# design.net
KiCad netlist of a schematic drawn in Altium Designer
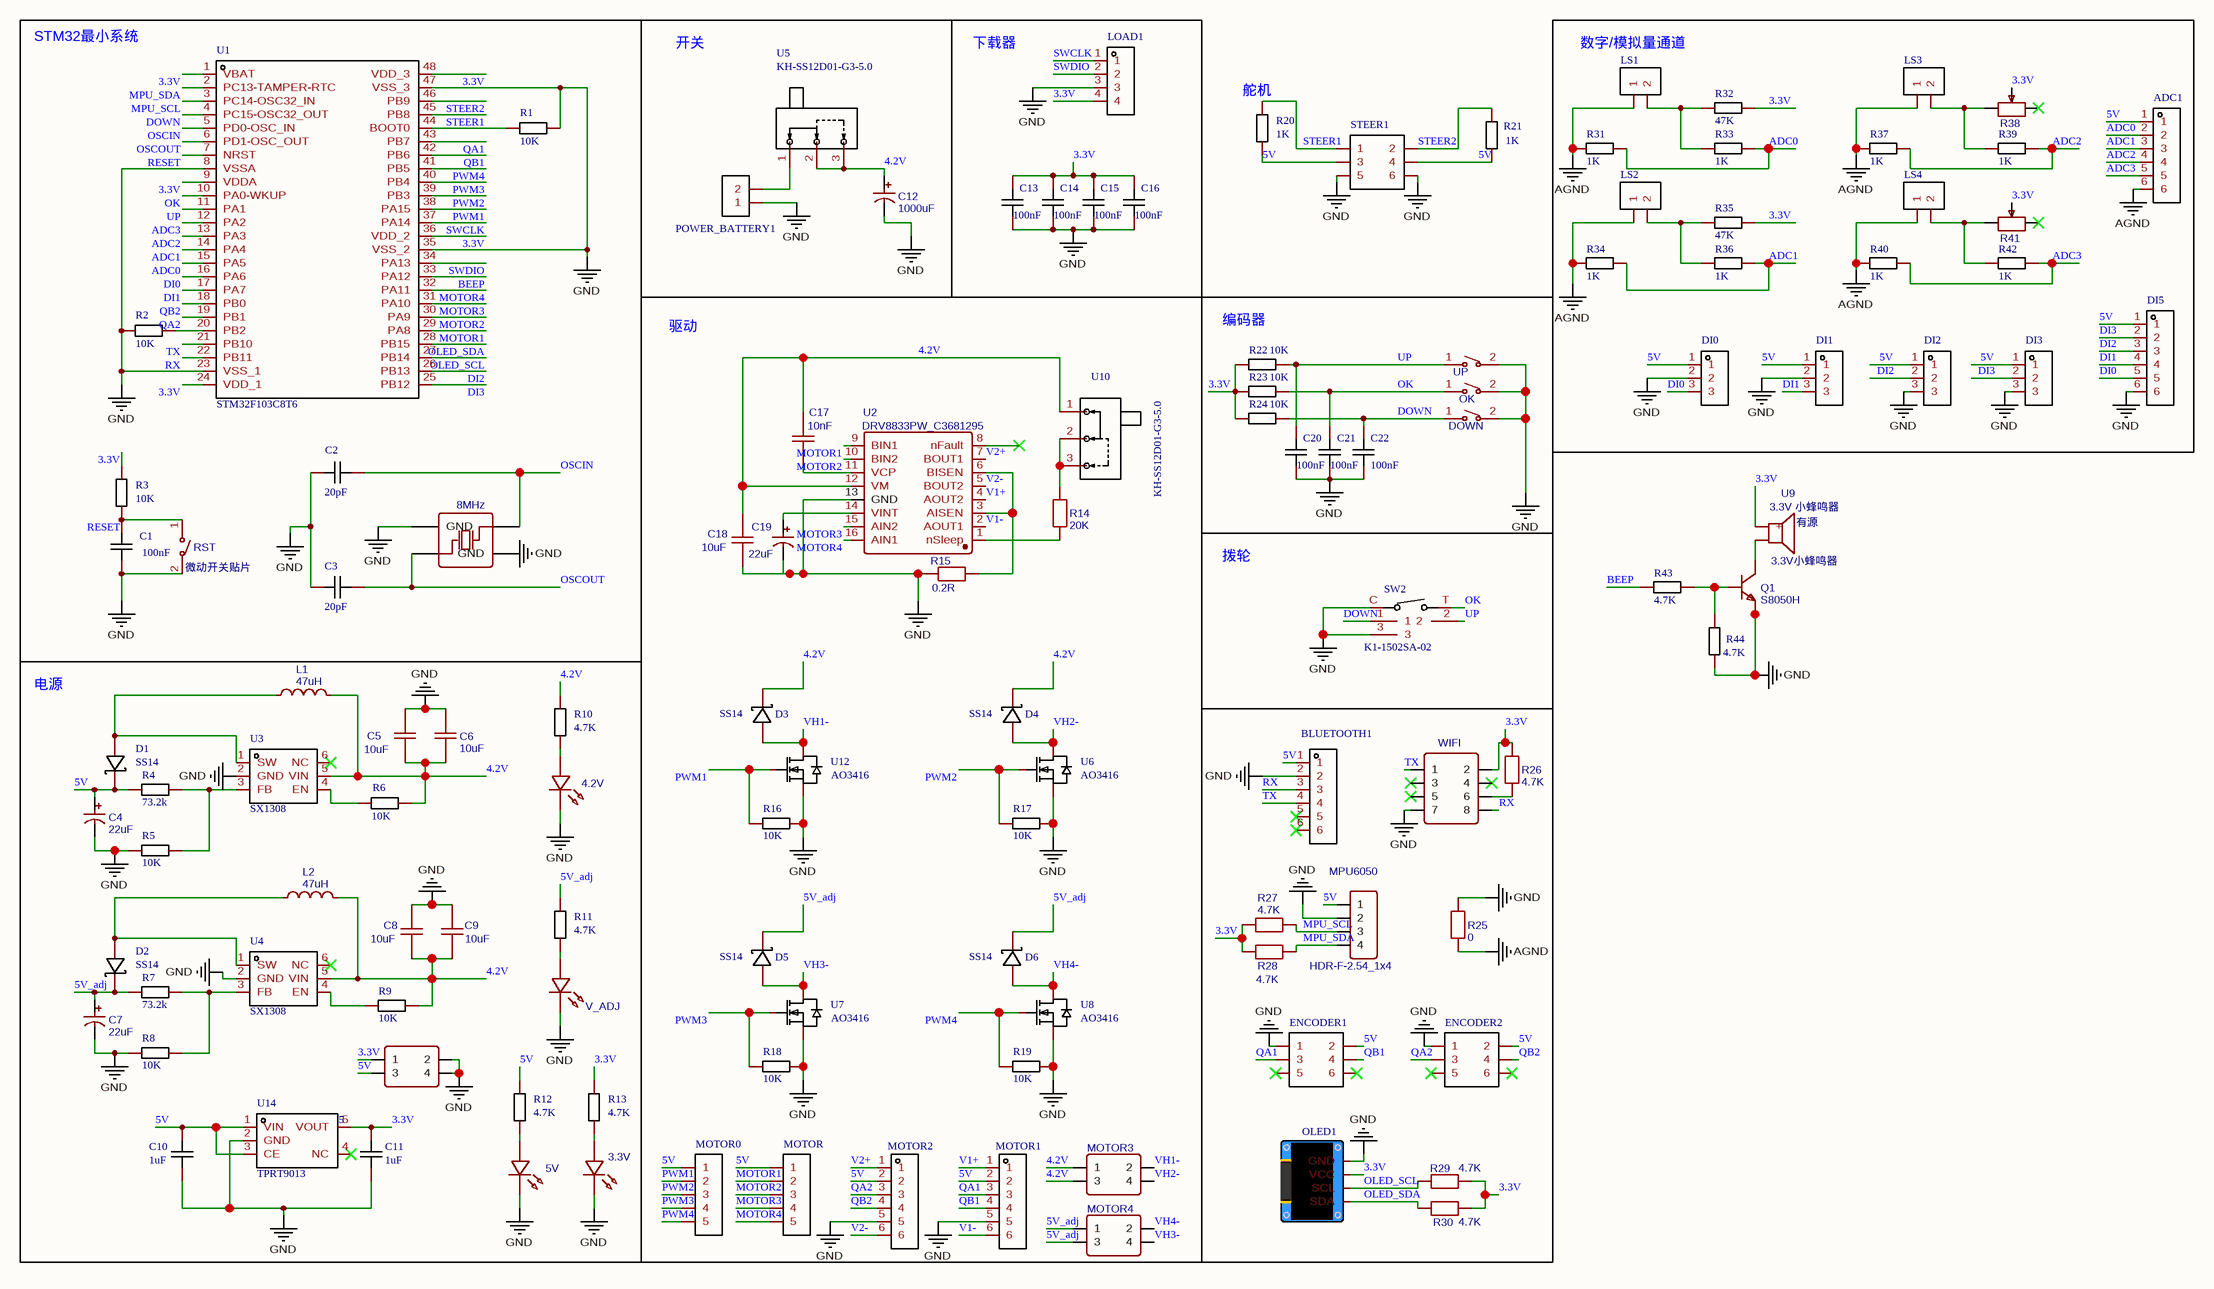
[diagram p0: 船主控原理图.schdoc]

(export (version "E")
  (design (tool "Eeschema 10.0.6"))
  (components
    (comp (ref "3.3V")
      (value "LED-0603_R")
      (fields
        (field (name "BOM_MANUFACTURER PART") "19-217/R6C-AL1M2VY/3T")
        (field (name "BOM_SUPPLIER PART") "C72044")
        (field (name "CONTRIBUTOR") "LCEDA_01")
      )
      (libsource (lib "altium-import") (part "root_3_LED-0603_R_"))
    )
    (comp (ref "4.2V")
      (value "LED-0603_R")
      (fields
        (field (name "BOM_MANUFACTURER PART") "19-217/R6C-AL1M2VY/3T")
        (field (name "BOM_SUPPLIER PART") "C72044")
        (field (name "CONTRIBUTOR") "LCEDA_01")
      )
      (libsource (lib "altium-import") (part "root_3_LED-0603_R_"))
    )
    (comp (ref "5V")
      (value "LED-0603_R")
      (fields
        (field (name "BOM_MANUFACTURER PART") "19-217/R6C-AL1M2VY/3T")
        (field (name "BOM_SUPPLIER PART") "C72044")
        (field (name "CONTRIBUTOR") "LCEDA_01")
      )
      (libsource (lib "altium-import") (part "root_3_LED-0603_R_"))
    )
    (comp (ref "ADC1")
      (value "HDR-F_2.54_1x6P")
      (libsource (lib "altium-import") (part "root_0_HDR-F_2.54_1x6P_"))
    )
    (comp (ref "BLUETOOTH1")
      (value "HDR-F_2.54_1x6P")
      (libsource (lib "altium-import") (part "root_0_HDR-F_2.54_1x6P_"))
    )
    (comp (ref "C1") (value "100nF") (libsource (lib "altium-import") (part "root_1_100nF_")))
    (comp (ref "C2") (value "100nF") (libsource (lib "altium-import") (part "root_0_100nF_")))
    (comp (ref "C3") (value "100nF") (libsource (lib "altium-import") (part "root_0_100nF_")))
    (comp (ref "C4")
      (value "22uF")
      (fields
        (field (name "BOM_MANUFACTURER PART") "CA45-A-6.3V-22uF-M")
        (field (name "BOM_SUPPLIER PART") "C140378")
        (field (name "CONTRIBUTOR") "LCSC")
      )
      (libsource (lib "altium-import") (part "root_1_22uF_"))
    )
    (comp (ref "C5")
      (value "10uF")
      (fields (field (name "CONTRIBUTOR") "LCEDA_Lib"))
      (libsource (lib "altium-import") (part "root_1_10uF_"))
    )
    (comp (ref "C6")
      (value "10uF")
      (fields (field (name "CONTRIBUTOR") "LCEDA_Lib"))
      (libsource (lib "altium-import") (part "root_1_10uF_"))
    )
    (comp (ref "C7")
      (value "22uF")
      (fields
        (field (name "BOM_MANUFACTURER PART") "CA45-A-6.3V-22uF-M")
        (field (name "BOM_SUPPLIER PART") "C140378")
        (field (name "CONTRIBUTOR") "LCSC")
      )
      (libsource (lib "altium-import") (part "root_1_22uF_"))
    )
    (comp (ref "C8")
      (value "10uF")
      (fields (field (name "CONTRIBUTOR") "LCEDA_Lib"))
      (libsource (lib "altium-import") (part "root_1_10uF_"))
    )
    (comp (ref "C9")
      (value "10uF")
      (fields (field (name "CONTRIBUTOR") "LCEDA_Lib"))
      (libsource (lib "altium-import") (part "root_1_10uF_"))
    )
    (comp (ref "C10") (value "1uF") (libsource (lib "altium-import") (part "root_1_1uF_")))
    (comp (ref "C11") (value "1uF") (libsource (lib "altium-import") (part "root_1_1uF_")))
    (comp (ref "C12")
      (value "1000uF")
      (fields
        (field (name "BOM_MANUFACTURER PART") "GR108M016F16RR0VL4FP0")
        (field (name "BOM_SUPPLIER PART") "C43834")
      )
      (libsource (lib "altium-import") (part "root_3_1000uF_"))
    )
    (comp (ref "C13") (value "100nF") (libsource (lib "altium-import") (part "root_1_100nF_")))
    (comp (ref "C14") (value "100nF") (libsource (lib "altium-import") (part "root_1_100nF_")))
    (comp (ref "C15") (value "100nF") (libsource (lib "altium-import") (part "root_1_100nF_")))
    (comp (ref "C16") (value "100nF") (libsource (lib "altium-import") (part "root_1_100nF_")))
    (comp (ref "C17")
      (value "10nF")
      (fields (field (name "CONTRIBUTOR") "LCEDA_Lib"))
      (libsource (lib "altium-import") (part "root_1_10nF_"))
    )
    (comp (ref "C18")
      (value "10uF")
      (fields (field (name "CONTRIBUTOR") "LCEDA_Lib"))
      (libsource (lib "altium-import") (part "root_1_10uF_"))
    )
    (comp (ref "C19")
      (value "22uF")
      (fields
        (field (name "BOM_MANUFACTURER PART") "CA45-A-6.3V-22uF-M")
        (field (name "BOM_SUPPLIER PART") "C140378")
        (field (name "CONTRIBUTOR") "LCSC")
      )
      (libsource (lib "altium-import") (part "root_1_22uF_"))
    )
    (comp (ref "C20") (value "100nF") (libsource (lib "altium-import") (part "root_1_100nF_")))
    (comp (ref "C21") (value "100nF") (libsource (lib "altium-import") (part "root_3_100nF_")))
    (comp (ref "C22") (value "100nF") (libsource (lib "altium-import") (part "root_1_100nF_")))
    (comp (ref "D1")
      (value "SS14")
      (fields (field (name "MANUFACTURER") "onsemi(安森美)"))
      (libsource (lib "altium-import") (part "root_1_SS14_"))
    )
    (comp (ref "D2")
      (value "SS14")
      (fields (field (name "MANUFACTURER") "onsemi(安森美)"))
      (libsource (lib "altium-import") (part "root_1_SS14_"))
    )
    (comp (ref "D3")
      (value "SS14")
      (fields (field (name "MANUFACTURER") "onsemi(安森美)"))
      (libsource (lib "altium-import") (part "root_3_SS14_"))
    )
    (comp (ref "D4")
      (value "SS14")
      (fields (field (name "MANUFACTURER") "onsemi(安森美)"))
      (libsource (lib "altium-import") (part "root_3_SS14_"))
    )
    (comp (ref "D5")
      (value "SS14")
      (fields (field (name "MANUFACTURER") "onsemi(安森美)"))
      (libsource (lib "altium-import") (part "root_3_SS14_"))
    )
    (comp (ref "D6")
      (value "SS14")
      (fields (field (name "MANUFACTURER") "onsemi(安森美)"))
      (libsource (lib "altium-import") (part "root_3_SS14_"))
    )
    (comp (ref "DI0")
      (value "HDR-F_2.54_1x3P")
      (libsource (lib "altium-import") (part "root_0_HDR-F_2.54_1x3P_"))
    )
    (comp (ref "DI1")
      (value "HDR-F_2.54_1x3P")
      (libsource (lib "altium-import") (part "root_0_HDR-F_2.54_1x3P_"))
    )
    (comp (ref "DI2")
      (value "HDR-F_2.54_1x3P")
      (libsource (lib "altium-import") (part "root_0_HDR-F_2.54_1x3P_"))
    )
    (comp (ref "DI3")
      (value "HDR-F_2.54_1x3P")
      (libsource (lib "altium-import") (part "root_0_HDR-F_2.54_1x3P_"))
    )
    (comp (ref "DI5")
      (value "HDR-F_2.54_1x6P")
      (libsource (lib "altium-import") (part "root_0_HDR-F_2.54_1x6P_"))
    )
    (comp (ref "DOWN")
      (value "微动开关贴片")
      (fields (field (name "BOM_SUPPLIER PART") "C9900003994") (field (name "CONTRIBUTOR") "LCSC"))
      (libsource (lib "altium-import") (part "root_0_微动开关贴片_"))
    )
    (comp (ref "ENCODER1")
      (value "HDR-F_2.54_2x3")
      (libsource (lib "altium-import") (part "root_0_HDR-F_2.54_2x3_"))
    )
    (comp (ref "ENCODER2")
      (value "HDR-F_2.54_2x3")
      (libsource (lib "altium-import") (part "root_0_HDR-F_2.54_2x3_"))
    )
    (comp (ref "H1")
      (value "HDR-F-2.54_2x2")
      (fields (field (name "BOM_SUPPLIER PART") "C239342") (field (name "CONTRIBUTOR") "LCEDA_Lib"))
      (libsource (lib "altium-import") (part "root_0_HDR-F-2.54_2x2_"))
    )
    (comp (ref "L1")
      (value "47uH")
      (fields
        (field (name "BOM_SUPPLIER PART") "C9900014391")
        (field (name "BOM_MANUFACTURER PART") "CDRH74R-7*7*4MM")
        (field (name "CONTRIBUTOR") "lcsc")
      )
      (libsource (lib "altium-import") (part "root_0_47uH_"))
    )
    (comp (ref "L2")
      (value "47uH")
      (fields
        (field (name "BOM_SUPPLIER PART") "C9900014391")
        (field (name "BOM_MANUFACTURER PART") "CDRH74R-7*7*4MM")
        (field (name "CONTRIBUTOR") "lcsc")
      )
      (libsource (lib "altium-import") (part "root_0_47uH_"))
    )
    (comp (ref "LOAD1")
      (value "HDR-F_2.54_1x4P")
      (libsource (lib "altium-import") (part "root_0_HDR-F_2.54_1x4P_"))
    )
    (comp (ref "LS1")
      (value "HDR-F_2.54_1x2P")
      (libsource (lib "altium-import") (part "root_1_HDR-F_2.54_1x2P_"))
    )
    (comp (ref "LS2")
      (value "HDR-F_2.54_1x2P")
      (libsource (lib "altium-import") (part "root_1_HDR-F_2.54_1x2P_"))
    )
    (comp (ref "LS3")
      (value "HDR-F_2.54_1x2P")
      (libsource (lib "altium-import") (part "root_1_HDR-F_2.54_1x2P_"))
    )
    (comp (ref "LS4")
      (value "HDR-F_2.54_1x2P")
      (libsource (lib "altium-import") (part "root_1_HDR-F_2.54_1x2P_"))
    )
    (comp (ref "MOTOR")
      (value "HDR-F_2.54_1x5P")
      (libsource (lib "altium-import") (part "root_0_HDR-F_2.54_1x5P_"))
    )
    (comp (ref "MOTOR0")
      (value "HDR-F_2.54_1x5P")
      (libsource (lib "altium-import") (part "root_0_HDR-F_2.54_1x5P_"))
    )
    (comp (ref "MOTOR1") (value "HDR-F_2.54_1x6P") (libsource (lib "") (part "root_0_HDR-F_2.54_1x6P__1")))
    (comp (ref "MOTOR2") (value "HDR-F_2.54_1x6P") (libsource (lib "") (part "root_0_HDR-F_2.54_1x6P__1")))
    (comp (ref "MOTOR3")
      (value "HDR-F-2.54_2x2")
      (fields (field (name "BOM_SUPPLIER PART") "C239342") (field (name "CONTRIBUTOR") "LCEDA_Lib"))
      (libsource (lib "altium-import") (part "root_0_HDR-F-2.54_2x2_"))
    )
    (comp (ref "MOTOR4")
      (value "HDR-F-2.54_2x2")
      (fields (field (name "BOM_SUPPLIER PART") "C239342") (field (name "CONTRIBUTOR") "LCEDA_Lib"))
      (libsource (lib "altium-import") (part "root_0_HDR-F-2.54_2x2_"))
    )
    (comp (ref "MPU6050")
      (value "HDR-F-2.54_1x4")
      (fields (field (name "BOM_SUPPLIER PART") "C225501") (field (name "CONTRIBUTOR") "LCEDA_Lib"))
      (libsource (lib "altium-import") (part "root_0_HDR-F-2.54_1x4_"))
    )
    (comp (ref "NO1")
      (value "8MHz")
      (fields
        (field (name "BOM_MANUFACTURER PART") "8M-3225G封装")
        (field (name "BOM_SUPPLIER PART") "无源晶振8M-3225")
        (field (name "CONTRIBUTOR") "BaoXiWang")
      )
      (libsource (lib "altium-import") (part "root_0_8MHz_"))
    )
    (comp (ref "OK")
      (value "微动开关贴片")
      (fields (field (name "BOM_SUPPLIER PART") "C9900003994") (field (name "CONTRIBUTOR") "LCSC"))
      (libsource (lib "altium-import") (part "root_0_微动开关贴片_"))
    )
    (comp (ref "OLED1")
      (value "0.96OLED模块_4P")
      (libsource (lib "altium-import") (part "root_3_0.96OLED模块_4P_"))
    )
    (comp (ref "POWER_BATTERY1")
      (value "HDR-F_2.54_1x2P")
      (libsource (lib "altium-import") (part "root_2_HDR-F_2.54_1x2P_"))
    )
    (comp (ref "Q1")
      (value "S8050H")
      (fields (field (name "BOM_SUPPLIER PART") "C388539") (field (name "CONTRIBUTOR") "LCSC"))
      (libsource (lib "altium-import") (part "root_0_S8050H_"))
    )
    (comp (ref "R1") (value "10K") (libsource (lib "altium-import") (part "root_0_10K_")))
    (comp (ref "R2") (value "10K") (libsource (lib "altium-import") (part "root_0_10K_")))
    (comp (ref "R3") (value "10K") (libsource (lib "altium-import") (part "root_1_10K_")))
    (comp (ref "R4") (value "3K") (libsource (lib "altium-import") (part "root_2_3K_")))
    (comp (ref "R5") (value "2K") (libsource (lib "altium-import") (part "root_2_2K_")))
    (comp (ref "R6") (value "10K") (libsource (lib "altium-import") (part "root_2_10K_")))
    (comp (ref "R7") (value "1K") (libsource (lib "altium-import") (part "root_2_1K_")))
    (comp (ref "R8") (value "3K") (libsource (lib "altium-import") (part "root_2_3K_")))
    (comp (ref "R9") (value "10K") (libsource (lib "altium-import") (part "root_2_10K_")))
    (comp (ref "R10") (value "4.7K") (libsource (lib "altium-import") (part "root_1_4.7K_")))
    (comp (ref "R11") (value "4.7K") (libsource (lib "altium-import") (part "root_1_4.7K_")))
    (comp (ref "R12") (value "4.7K") (libsource (lib "altium-import") (part "root_1_4.7K_")))
    (comp (ref "R13") (value "4.7K") (libsource (lib "altium-import") (part "root_1_4.7K_")))
    (comp (ref "R14")
      (value "20K")
      (fields (field (name "CONTRIBUTOR") "LCEDA_Lib"))
      (libsource (lib "altium-import") (part "root_1_20K_"))
    )
    (comp (ref "R15")
      (value "0.2R")
      (fields (field (name "CONTRIBUTOR") "LCEDA_Lib"))
      (libsource (lib "altium-import") (part "root_0_0.2R_"))
    )
    (comp (ref "R16") (value "10K") (libsource (lib "altium-import") (part "root_2_10K_")))
    (comp (ref "R17") (value "10K") (libsource (lib "altium-import") (part "root_2_10K_")))
    (comp (ref "R18") (value "10K") (libsource (lib "altium-import") (part "root_2_10K_")))
    (comp (ref "R19") (value "10K") (libsource (lib "altium-import") (part "root_2_10K_")))
    (comp (ref "R20") (value "1K") (libsource (lib "altium-import") (part "root_3_1K_")))
    (comp (ref "R21") (value "1K") (libsource (lib "altium-import") (part "root_3_1K_")))
    (comp (ref "R22") (value "10K") (libsource (lib "altium-import") (part "root_2_10K_")))
    (comp (ref "R23") (value "10K") (libsource (lib "altium-import") (part "root_2_10K_")))
    (comp (ref "R24") (value "10K") (libsource (lib "altium-import") (part "root_2_10K_")))
    (comp (ref "R25")
      (value "0")
      (fields (field (name "CONTRIBUTOR") "LCEDA_Lib"))
      (libsource (lib "altium-import") (part "root_1_0_"))
    )
    (comp (ref "R26")
      (value "4.7K")
      (fields (field (name "CONTRIBUTOR") "LCEDA_Lib"))
      (libsource (lib "") (part "root_1_4.7K__1"))
    )
    (comp (ref "R27")
      (value "4.7K")
      (fields (field (name "CONTRIBUTOR") "LCEDA_Lib"))
      (libsource (lib "altium-import") (part "root_0_4.7K_"))
    )
    (comp (ref "R28")
      (value "4.7K")
      (fields (field (name "CONTRIBUTOR") "LCEDA_Lib"))
      (libsource (lib "altium-import") (part "root_0_4.7K_"))
    )
    (comp (ref "R29")
      (value "4.7K")
      (fields (field (name "CONTRIBUTOR") "LCEDA_Lib"))
      (libsource (lib "altium-import") (part "root_2_4.7K_"))
    )
    (comp (ref "R30")
      (value "4.7K")
      (fields (field (name "CONTRIBUTOR") "LCEDA_Lib"))
      (libsource (lib "altium-import") (part "root_2_4.7K_"))
    )
    (comp (ref "R31") (value "1K") (libsource (lib "altium-import") (part "root_0_1K_")))
    (comp (ref "R32") (value "47K") (libsource (lib "altium-import") (part "root_2_47K_")))
    (comp (ref "R33") (value "1K") (libsource (lib "altium-import") (part "root_0_1K_")))
    (comp (ref "R34") (value "1K") (libsource (lib "altium-import") (part "root_0_1K_")))
    (comp (ref "R35") (value "47K") (libsource (lib "altium-import") (part "root_2_47K_")))
    (comp (ref "R36") (value "1K") (libsource (lib "altium-import") (part "root_0_1K_")))
    (comp (ref "R37") (value "1K") (libsource (lib "altium-import") (part "root_0_1K_")))
    (comp (ref "R38")
      (value "3296W-2K")
      (fields (field (name "BOM_SUPPLIER PART") "C9900022608") (field (name "CONTRIBUTOR") "lcsc"))
      (libsource (lib "altium-import") (part "root_3_3296W-2K_"))
    )
    (comp (ref "R39") (value "1K") (libsource (lib "altium-import") (part "root_0_1K_")))
    (comp (ref "R40") (value "1K") (libsource (lib "altium-import") (part "root_0_1K_")))
    (comp (ref "R41")
      (value "3296W-2K")
      (fields (field (name "BOM_SUPPLIER PART") "C9900022608") (field (name "CONTRIBUTOR") "lcsc"))
      (libsource (lib "altium-import") (part "root_3_3296W-2K_"))
    )
    (comp (ref "R42") (value "1K") (libsource (lib "altium-import") (part "root_0_1K_")))
    (comp (ref "R43") (value "1K") (libsource (lib "altium-import") (part "root_0_1K_")))
    (comp (ref "R44") (value "1K") (libsource (lib "altium-import") (part "root_1_1K_")))
    (comp (ref "RST")
      (value "微动开关贴片")
      (fields (field (name "BOM_SUPPLIER PART") "C9900003994") (field (name "CONTRIBUTOR") "LCSC"))
      (libsource (lib "altium-import") (part "root_3_微动开关贴片_"))
    )
    (comp (ref "STEER1")
      (value "HDR-F_2.54_2x3")
      (libsource (lib "altium-import") (part "root_0_HDR-F_2.54_2x3_"))
    )
    (comp (ref "SW2")
      (value "K1-1502SA-02")
      (fields (field (name "MANUFACTURER") "韩国韩荣"))
      (libsource (lib "altium-import") (part "root_0_K1-1502SA-02_"))
    )
    (comp (ref "U1")
      (value "STM32F103C8T6")
      (fields (field (name "MANUFACTURER") "ST(意法半导体)"))
      (libsource (lib "altium-import") (part "root_0_STM32F103C8T6_"))
    )
    (comp (ref "U2")
      (value "DRV8833PW_C3681295")
      (fields
        (field (name "BOM_SUPPLIER PART") "C3681295")
        (field (name "BOM_MANUFACTURER PART") "DRV8833PW")
        (field (name "CONTRIBUTOR") "lcsc")
      )
      (libsource (lib "altium-import") (part "root_2_DRV8833PW_C3681295_"))
    )
    (comp (ref "U3")
      (value "SX1308")
      (fields (field (name "MANUFACTURER") "SX(硕芯科技)"))
      (libsource (lib "altium-import") (part "root_0_SX1308_"))
    )
    (comp (ref "U4")
      (value "SX1308")
      (fields (field (name "MANUFACTURER") "SX(硕芯科技)"))
      (libsource (lib "altium-import") (part "root_0_SX1308_"))
    )
    (comp (ref "U5")
      (value "KH-SS12D01-G3-5.0")
      (fields (field (name "MANUFACTURER") "kinghelm(金航标)"))
      (libsource (lib "altium-import") (part "root_0_KH-SS12D01-G3-5.0_"))
    )
    (comp (ref "U6")
      (value "AO3416")
      (fields (field (name "MANUFACTURER") "BORN(伯恩半导体)"))
      (libsource (lib "altium-import") (part "root_0_AO3416_"))
    )
    (comp (ref "U7")
      (value "AO3416")
      (fields (field (name "MANUFACTURER") "BORN(伯恩半导体)"))
      (libsource (lib "altium-import") (part "root_0_AO3416_"))
    )
    (comp (ref "U8")
      (value "AO3416")
      (fields (field (name "MANUFACTURER") "BORN(伯恩半导体)"))
      (libsource (lib "altium-import") (part "root_0_AO3416_"))
    )
    (comp (ref "U9")
      (value "3.3V 小蜂鸣器")
      (fields (field (name "CONTRIBUTOR") "oyhoyh"))
      (libsource (lib "altium-import") (part "root_0_3.3V 小蜂鸣器_"))
    )
    (comp (ref "U10")
      (value "KH-SS12D01-G3-5.0")
      (fields (field (name "MANUFACTURER") "kinghelm(金航标)"))
      (libsource (lib "altium-import") (part "root_3_KH-SS12D01-G3-5.0_"))
    )
    (comp (ref "U12")
      (value "AO3416")
      (fields (field (name "MANUFACTURER") "BORN(伯恩半导体)"))
      (libsource (lib "altium-import") (part "root_0_AO3416_"))
    )
    (comp (ref "U14")
      (value "TPRT9013")
      (fields (field (name "MANUFACTURER") "TECH PUBLIC(台舟)"))
      (libsource (lib "altium-import") (part "root_0_TPRT9013_"))
    )
    (comp (ref "UP")
      (value "微动开关贴片")
      (fields (field (name "BOM_SUPPLIER PART") "C9900003994") (field (name "CONTRIBUTOR") "LCSC"))
      (libsource (lib "altium-import") (part "root_0_微动开关贴片_"))
    )
    (comp (ref "V_ADJ")
      (value "LED-0603_R")
      (fields
        (field (name "BOM_MANUFACTURER PART") "19-217/R6C-AL1M2VY/3T")
        (field (name "BOM_SUPPLIER PART") "C72044")
        (field (name "CONTRIBUTOR") "LCEDA_01")
      )
      (libsource (lib "altium-import") (part "root_3_LED-0603_R_"))
    )
    (comp (ref "WIFI")
      (value "HDR-M-2.54_2x4")
      (fields (field (name "BOM_SUPPLIER PART") "C58363") (field (name "CONTRIBUTOR") "LCEDA_Lib"))
      (libsource (lib "altium-import") (part "root_0_HDR-M-2.54_2x4_"))
    )
  )
  (nets
    (net (code "1") (name "/3.3V") (class "Default")
      (node (ref "C11") (pin "2") (pinfunction "2_2") (pintype "passive"))
      (node (ref "C13") (pin "2") (pinfunction "2_2") (pintype "passive"))
      (node (ref "C14") (pin "2") (pinfunction "2_2") (pintype "passive"))
      (node (ref "C15") (pin "2") (pinfunction "2_2") (pintype "passive"))
      (node (ref "C16") (pin "2") (pinfunction "2_2") (pintype "passive"))
      (node (ref "H1") (pin "1") (pinfunction "1_1") (pintype "passive"))
      (node (ref "LOAD1") (pin "4") (pinfunction "4_4") (pintype "passive"))
      (node (ref "OLED1") (pin "2") (pinfunction "VCC_2") (pintype "passive"))
      (node (ref "R13") (pin "2") (pinfunction "2_2") (pintype "passive"))
      (node (ref "R22") (pin "2") (pinfunction "2_2") (pintype "passive"))
      (node (ref "R23") (pin "2") (pinfunction "2_2") (pintype "passive"))
      (node (ref "R24") (pin "2") (pinfunction "2_2") (pintype "passive"))
      (node (ref "R26") (pin "2") (pinfunction "2_2") (pintype "passive"))
      (node (ref "R27") (pin "1") (pinfunction "1_1") (pintype "passive"))
      (node (ref "R28") (pin "1") (pinfunction "1_1") (pintype "passive"))
      (node (ref "R29") (pin "1") (pinfunction "1_1") (pintype "passive"))
      (node (ref "R3") (pin "2") (pinfunction "2_2") (pintype "passive"))
      (node (ref "R30") (pin "1") (pinfunction "1_1") (pintype "passive"))
      (node (ref "R32") (pin "1") (pinfunction "1_1") (pintype "passive"))
      (node (ref "R35") (pin "1") (pinfunction "1_1") (pintype "passive"))
      (node (ref "R38") (pin "2") (pinfunction "2_2") (pintype "passive"))
      (node (ref "R41") (pin "2") (pinfunction "2_2") (pintype "passive"))
      (node (ref "U1") (pin "1") (pinfunction "VBAT_1") (pintype "passive"))
      (node (ref "U1") (pin "24") (pinfunction "VDD_1_24") (pintype "passive"))
      (node (ref "U1") (pin "36") (pinfunction "VDD_2_36") (pintype "passive"))
      (node (ref "U1") (pin "48") (pinfunction "VDD_3_48") (pintype "passive"))
      (node (ref "U1") (pin "9") (pinfunction "VDDA_9") (pintype "passive"))
      (node (ref "U14") (pin "5") (pinfunction "VOUT_5") (pintype "passive"))
      (node (ref "U9") (pin "1") (pinfunction "+_1") (pintype "passive"))
      (node (ref "WIFI") (pin "2") (pinfunction "2_2") (pintype "passive"))
    )
    (net (code "2") (name "/4.2V") (class "Default")
      (node (ref "C12") (pin "1") (pinfunction "1_1") (pintype "passive"))
      (node (ref "C17") (pin "2") (pinfunction "2_2") (pintype "passive"))
      (node (ref "C18") (pin "2") (pinfunction "2_2") (pintype "passive"))
      (node (ref "C5") (pin "1") (pinfunction "1_1") (pintype "passive"))
      (node (ref "C6") (pin "1") (pinfunction "1_1") (pintype "passive"))
      (node (ref "C8") (pin "1") (pinfunction "1_1") (pintype "passive"))
      (node (ref "C9") (pin "1") (pinfunction "1_1") (pintype "passive"))
      (node (ref "D3") (pin "1") (pinfunction "K_1") (pintype "passive"))
      (node (ref "D4") (pin "1") (pinfunction "K_1") (pintype "passive"))
      (node (ref "L1") (pin "2") (pinfunction "2_2") (pintype "passive"))
      (node (ref "L2") (pin "2") (pinfunction "2_2") (pintype "passive"))
      (node (ref "MOTOR3") (pin "1") (pinfunction "1_1") (pintype "passive"))
      (node (ref "MOTOR3") (pin "3") (pinfunction "3_3") (pintype "passive"))
      (node (ref "R10") (pin "2") (pinfunction "2_2") (pintype "passive"))
      (node (ref "R6") (pin "1") (pinfunction "1_1") (pintype "passive"))
      (node (ref "R9") (pin "1") (pinfunction "1_1") (pintype "passive"))
      (node (ref "U10") (pin "1") (pinfunction "1_1") (pintype "passive"))
      (node (ref "U2") (pin "12") (pinfunction "VM_12") (pintype "passive"))
      (node (ref "U3") (pin "5") (pinfunction "VIN_5") (pintype "passive"))
      (node (ref "U4") (pin "5") (pinfunction "VIN_5") (pintype "passive"))
      (node (ref "U5") (pin "2") (pinfunction "2_2") (pintype "passive"))
      (node (ref "U5") (pin "3") (pinfunction "3_3") (pintype "passive"))
    )
    (net (code "3") (name "/5V") (class "Default")
      (node (ref "ADC1") (pin "1") (pinfunction "1_1") (pintype "passive"))
      (node (ref "BLUETOOTH1") (pin "1") (pinfunction "1_1") (pintype "passive"))
      (node (ref "C10") (pin "2") (pinfunction "2_2") (pintype "passive"))
      (node (ref "C4") (pin "1") (pinfunction "1_1") (pintype "passive"))
      (node (ref "D1") (pin "1") (pinfunction "K_1") (pintype "passive"))
      (node (ref "DI0") (pin "1") (pinfunction "1_1") (pintype "passive"))
      (node (ref "DI1") (pin "1") (pinfunction "1_1") (pintype "passive"))
      (node (ref "DI2") (pin "1") (pinfunction "1_1") (pintype "passive"))
      (node (ref "DI3") (pin "1") (pinfunction "1_1") (pintype "passive"))
      (node (ref "DI5") (pin "1") (pinfunction "1_1") (pintype "passive"))
      (node (ref "ENCODER1") (pin "2") (pinfunction "2_2") (pintype "passive"))
      (node (ref "ENCODER2") (pin "2") (pinfunction "2_2") (pintype "passive"))
      (node (ref "H1") (pin "3") (pinfunction "3_3") (pintype "passive"))
      (node (ref "MOTOR") (pin "1") (pinfunction "1_1") (pintype "passive"))
      (node (ref "MOTOR0") (pin "1") (pinfunction "1_1") (pintype "passive"))
      (node (ref "MOTOR1") (pin "2") (pinfunction "2_2") (pintype "passive"))
      (node (ref "MOTOR2") (pin "2") (pinfunction "2_2") (pintype "passive"))
      (node (ref "MPU6050") (pin "1") (pinfunction "1_1") (pintype "passive"))
      (node (ref "R12") (pin "2") (pinfunction "2_2") (pintype "passive"))
      (node (ref "R20") (pin "2") (pinfunction "2_2") (pintype "passive"))
      (node (ref "R21") (pin "2") (pinfunction "2_2") (pintype "passive"))
      (node (ref "R4") (pin "2") (pinfunction "2_2") (pintype "passive"))
      (node (ref "STEER1") (pin "3") (pinfunction "3_3") (pintype "passive"))
      (node (ref "STEER1") (pin "4") (pinfunction "4_4") (pintype "passive"))
      (node (ref "U14") (pin "1") (pinfunction "VIN_1") (pintype "passive"))
      (node (ref "U14") (pin "3") (pinfunction "CE_3") (pintype "passive"))
    )
    (net (code "4") (name "/5V_adj") (class "Default")
      (node (ref "C7") (pin "1") (pinfunction "1_1") (pintype "passive"))
      (node (ref "D2") (pin "1") (pinfunction "K_1") (pintype "passive"))
      (node (ref "D5") (pin "1") (pinfunction "K_1") (pintype "passive"))
      (node (ref "D6") (pin "1") (pinfunction "K_1") (pintype "passive"))
      (node (ref "MOTOR4") (pin "1") (pinfunction "1_1") (pintype "passive"))
      (node (ref "MOTOR4") (pin "3") (pinfunction "3_3") (pintype "passive"))
      (node (ref "R11") (pin "2") (pinfunction "2_2") (pintype "passive"))
      (node (ref "R7") (pin "2") (pinfunction "2_2") (pintype "passive"))
    )
    (net (code "5") (name "/ADC0") (class "Default")
      (node (ref "ADC1") (pin "2") (pinfunction "2_2") (pintype "passive"))
      (node (ref "R31") (pin "2") (pinfunction "2_2") (pintype "passive"))
      (node (ref "R33") (pin "2") (pinfunction "2_2") (pintype "passive"))
      (node (ref "U1") (pin "15") (pinfunction "PA5_15") (pintype "passive"))
    )
    (net (code "6") (name "/ADC1") (class "Default")
      (node (ref "ADC1") (pin "3") (pinfunction "3_3") (pintype "passive"))
      (node (ref "R34") (pin "2") (pinfunction "2_2") (pintype "passive"))
      (node (ref "R36") (pin "2") (pinfunction "2_2") (pintype "passive"))
      (node (ref "U1") (pin "14") (pinfunction "PA4_14") (pintype "passive"))
    )
    (net (code "7") (name "/ADC2") (class "Default")
      (node (ref "ADC1") (pin "4") (pinfunction "4_4") (pintype "passive"))
      (node (ref "R37") (pin "2") (pinfunction "2_2") (pintype "passive"))
      (node (ref "R39") (pin "2") (pinfunction "2_2") (pintype "passive"))
      (node (ref "U1") (pin "13") (pinfunction "PA3_13") (pintype "passive"))
    )
    (net (code "8") (name "/ADC3") (class "Default")
      (node (ref "ADC1") (pin "5") (pinfunction "5_5") (pintype "passive"))
      (node (ref "R40") (pin "2") (pinfunction "2_2") (pintype "passive"))
      (node (ref "R42") (pin "2") (pinfunction "2_2") (pintype "passive"))
      (node (ref "U1") (pin "12") (pinfunction "PA2_12") (pintype "passive"))
    )
    (net (code "9") (name "/BEEP") (class "Default")
      (node (ref "R43") (pin "1") (pinfunction "1_1") (pintype "passive"))
      (node (ref "U1") (pin "33") (pinfunction "PA12_33") (pintype "passive"))
    )
    (net (code "10") (name "/DI0") (class "Default")
      (node (ref "DI0") (pin "3") (pinfunction "3_3") (pintype "passive"))
      (node (ref "DI5") (pin "5") (pinfunction "5_5") (pintype "passive"))
      (node (ref "U1") (pin "16") (pinfunction "PA6_16") (pintype "passive"))
    )
    (net (code "11") (name "/DI1") (class "Default")
      (node (ref "DI1") (pin "3") (pinfunction "3_3") (pintype "passive"))
      (node (ref "DI5") (pin "4") (pinfunction "4_4") (pintype "passive"))
      (node (ref "U1") (pin "17") (pinfunction "PA7_17") (pintype "passive"))
    )
    (net (code "12") (name "/DI2") (class "Default")
      (node (ref "DI2") (pin "2") (pinfunction "2_2") (pintype "passive"))
      (node (ref "DI5") (pin "3") (pinfunction "3_3") (pintype "passive"))
      (node (ref "U1") (pin "26") (pinfunction "PB13_26") (pintype "passive"))
    )
    (net (code "13") (name "/DI3") (class "Default")
      (node (ref "DI3") (pin "2") (pinfunction "2_2") (pintype "passive"))
      (node (ref "DI5") (pin "2") (pinfunction "2_2") (pintype "passive"))
      (node (ref "U1") (pin "25") (pinfunction "PB12_25") (pintype "passive"))
    )
    (net (code "14") (name "/DOWN") (class "Default")
      (node (ref "C22") (pin "2") (pinfunction "2_2") (pintype "passive"))
      (node (ref "DOWN") (pin "1") (pinfunction "1_1") (pintype "passive"))
      (node (ref "R24") (pin "1") (pinfunction "1_1") (pintype "passive"))
      (node (ref "SW2") (pin "1") (pinfunction "1_1") (pintype "passive"))
      (node (ref "U1") (pin "4") (pinfunction "PC15-OSC32_OUT_4") (pintype "passive"))
    )
    (net (code "15") (name "/MOTOR1") (class "Default")
      (node (ref "MOTOR") (pin "2") (pinfunction "2_2") (pintype "passive"))
      (node (ref "U1") (pin "29") (pinfunction "PA8_29") (pintype "passive"))
      (node (ref "U2") (pin "9") (pinfunction "BIN1_9") (pintype "passive"))
    )
    (net (code "16") (name "/MOTOR2") (class "Default")
      (node (ref "MOTOR") (pin "3") (pinfunction "3_3") (pintype "passive"))
      (node (ref "U1") (pin "30") (pinfunction "PA9_30") (pintype "passive"))
      (node (ref "U2") (pin "10") (pinfunction "BIN2_10") (pintype "passive"))
    )
    (net (code "17") (name "/MOTOR3") (class "Default")
      (node (ref "MOTOR") (pin "4") (pinfunction "4_4") (pintype "passive"))
      (node (ref "U1") (pin "31") (pinfunction "PA10_31") (pintype "passive"))
      (node (ref "U2") (pin "15") (pinfunction "AIN2_15") (pintype "passive"))
    )
    (net (code "18") (name "/MOTOR4") (class "Default")
      (node (ref "MOTOR") (pin "5") (pinfunction "5_5") (pintype "passive"))
      (node (ref "U1") (pin "32") (pinfunction "PA11_32") (pintype "passive"))
      (node (ref "U2") (pin "16") (pinfunction "AIN1_16") (pintype "passive"))
    )
    (net (code "19") (name "/MPU_SCL") (class "Default")
      (node (ref "MPU6050") (pin "3") (pinfunction "3_3") (pintype "passive"))
      (node (ref "R27") (pin "2") (pinfunction "2_2") (pintype "passive"))
      (node (ref "U1") (pin "3") (pinfunction "PC14-OSC32_IN_3") (pintype "passive"))
    )
    (net (code "20") (name "/MPU_SDA") (class "Default")
      (node (ref "MPU6050") (pin "4") (pinfunction "4_4") (pintype "passive"))
      (node (ref "R28") (pin "2") (pinfunction "2_2") (pintype "passive"))
      (node (ref "U1") (pin "2") (pinfunction "PC13-TAMPER-RTC_2") (pintype "passive"))
    )
    (net (code "21") (name "/OK") (class "Default")
      (node (ref "C21") (pin "1") (pinfunction "1_1") (pintype "passive"))
      (node (ref "OK") (pin "1") (pinfunction "1_1") (pintype "passive"))
      (node (ref "R23") (pin "1") (pinfunction "1_1") (pintype "passive"))
      (node (ref "SW2") (pin "T") (pinfunction "T_T") (pintype "passive"))
      (node (ref "U1") (pin "10") (pinfunction "PA0-WKUP_10") (pintype "passive"))
    )
    (net (code "22") (name "/OLED_SCL") (class "Default")
      (node (ref "OLED1") (pin "3") (pinfunction "SCL_3") (pintype "passive"))
      (node (ref "R29") (pin "2") (pinfunction "2_2") (pintype "passive"))
      (node (ref "U1") (pin "27") (pinfunction "PB14_27") (pintype "passive"))
    )
    (net (code "23") (name "/OLED_SDA") (class "Default")
      (node (ref "OLED1") (pin "4") (pinfunction "SDA_4") (pintype "passive"))
      (node (ref "R30") (pin "2") (pinfunction "2_2") (pintype "passive"))
      (node (ref "U1") (pin "28") (pinfunction "PB15_28") (pintype "passive"))
    )
    (net (code "24") (name "/OSCIN") (class "Default")
      (node (ref "C2") (pin "2") (pinfunction "2_2") (pintype "passive"))
      (node (ref "NO1") (pin "3") (pinfunction "OSC2_3") (pintype "passive"))
      (node (ref "U1") (pin "5") (pinfunction "PD0-OSC_IN_5") (pintype "passive"))
    )
    (net (code "25") (name "/OSCOUT") (class "Default")
      (node (ref "C3") (pin "2") (pinfunction "2_2") (pintype "passive"))
      (node (ref "NO1") (pin "1") (pinfunction "OSC1_1") (pintype "passive"))
      (node (ref "U1") (pin "6") (pinfunction "PD1-OSC_OUT_6") (pintype "passive"))
    )
    (net (code "26") (name "/PWM1") (class "Default")
      (node (ref "MOTOR0") (pin "2") (pinfunction "2_2") (pintype "passive"))
      (node (ref "R16") (pin "2") (pinfunction "2_2") (pintype "passive"))
      (node (ref "U1") (pin "38") (pinfunction "PA15_38") (pintype "passive"))
      (node (ref "U12") (pin "1") (pinfunction "G_1") (pintype "passive"))
    )
    (net (code "27") (name "/PWM2") (class "Default")
      (node (ref "MOTOR0") (pin "3") (pinfunction "3_3") (pintype "passive"))
      (node (ref "R17") (pin "2") (pinfunction "2_2") (pintype "passive"))
      (node (ref "U1") (pin "39") (pinfunction "PB3_39") (pintype "passive"))
      (node (ref "U6") (pin "1") (pinfunction "G_1") (pintype "passive"))
    )
    (net (code "28") (name "/PWM3") (class "Default")
      (node (ref "MOTOR0") (pin "4") (pinfunction "4_4") (pintype "passive"))
      (node (ref "R18") (pin "2") (pinfunction "2_2") (pintype "passive"))
      (node (ref "U1") (pin "40") (pinfunction "PB4_40") (pintype "passive"))
      (node (ref "U7") (pin "1") (pinfunction "G_1") (pintype "passive"))
    )
    (net (code "29") (name "/PWM4") (class "Default")
      (node (ref "MOTOR0") (pin "5") (pinfunction "5_5") (pintype "passive"))
      (node (ref "R19") (pin "2") (pinfunction "2_2") (pintype "passive"))
      (node (ref "U1") (pin "41") (pinfunction "PB5_41") (pintype "passive"))
      (node (ref "U8") (pin "1") (pinfunction "G_1") (pintype "passive"))
    )
    (net (code "30") (name "/QA1") (class "Default")
      (node (ref "ENCODER1") (pin "3") (pinfunction "3_3") (pintype "passive"))
      (node (ref "MOTOR1") (pin "3") (pinfunction "3_3") (pintype "passive"))
      (node (ref "U1") (pin "43") (pinfunction "PB7_43") (pintype "passive"))
    )
    (net (code "31") (name "/QA2") (class "Default")
      (node (ref "ENCODER2") (pin "3") (pinfunction "3_3") (pintype "passive"))
      (node (ref "MOTOR2") (pin "3") (pinfunction "3_3") (pintype "passive"))
      (node (ref "U1") (pin "19") (pinfunction "PB1_19") (pintype "passive"))
    )
    (net (code "32") (name "/QB1") (class "Default")
      (node (ref "ENCODER1") (pin "4") (pinfunction "4_4") (pintype "passive"))
      (node (ref "MOTOR1") (pin "4") (pinfunction "4_4") (pintype "passive"))
      (node (ref "U1") (pin "42") (pinfunction "PB6_42") (pintype "passive"))
    )
    (net (code "33") (name "/QB2") (class "Default")
      (node (ref "ENCODER2") (pin "4") (pinfunction "4_4") (pintype "passive"))
      (node (ref "MOTOR2") (pin "4") (pinfunction "4_4") (pintype "passive"))
      (node (ref "U1") (pin "18") (pinfunction "PB0_18") (pintype "passive"))
    )
    (net (code "34") (name "/RESET") (class "Default")
      (node (ref "C1") (pin "2") (pinfunction "2_2") (pintype "passive"))
      (node (ref "R3") (pin "1") (pinfunction "1_1") (pintype "passive"))
      (node (ref "RST") (pin "1") (pinfunction "1_1") (pintype "passive"))
      (node (ref "U1") (pin "7") (pinfunction "NRST_7") (pintype "passive"))
    )
    (net (code "35") (name "/RX") (class "Default")
      (node (ref "BLUETOOTH1") (pin "3") (pinfunction "3_3") (pintype "passive"))
      (node (ref "U1") (pin "22") (pinfunction "PB11_22") (pintype "passive"))
      (node (ref "WIFI") (pin "8") (pinfunction "8_8") (pintype "passive"))
    )
    (net (code "36") (name "/STEER1") (class "Default")
      (node (ref "R20") (pin "1") (pinfunction "1_1") (pintype "passive"))
      (node (ref "STEER1") (pin "1") (pinfunction "1_1") (pintype "passive"))
      (node (ref "U1") (pin "45") (pinfunction "PB8_45") (pintype "passive"))
    )
    (net (code "37") (name "/STEER2") (class "Default")
      (node (ref "R21") (pin "1") (pinfunction "1_1") (pintype "passive"))
      (node (ref "STEER1") (pin "2") (pinfunction "2_2") (pintype "passive"))
      (node (ref "U1") (pin "46") (pinfunction "PB9_46") (pintype "passive"))
    )
    (net (code "38") (name "/SWCLK") (class "Default")
      (node (ref "LOAD1") (pin "1") (pinfunction "1_1") (pintype "passive"))
      (node (ref "U1") (pin "37") (pinfunction "PA14_37") (pintype "passive"))
    )
    (net (code "39") (name "/SWDIO") (class "Default")
      (node (ref "LOAD1") (pin "2") (pinfunction "2_2") (pintype "passive"))
      (node (ref "U1") (pin "34") (pinfunction "PA13_34") (pintype "passive"))
    )
    (net (code "40") (name "/TX") (class "Default")
      (node (ref "BLUETOOTH1") (pin "4") (pinfunction "4_4") (pintype "passive"))
      (node (ref "U1") (pin "21") (pinfunction "PB10_21") (pintype "passive"))
      (node (ref "WIFI") (pin "1") (pinfunction "1_1") (pintype "passive"))
    )
    (net (code "41") (name "/UP") (class "Default")
      (node (ref "C20") (pin "2") (pinfunction "2_2") (pintype "passive"))
      (node (ref "R22") (pin "1") (pinfunction "1_1") (pintype "passive"))
      (node (ref "SW2") (pin "2") (pinfunction "2_2") (pintype "passive"))
      (node (ref "U1") (pin "11") (pinfunction "PA1_11") (pintype "passive"))
      (node (ref "UP") (pin "1") (pinfunction "1_1") (pintype "passive"))
    )
    (net (code "42") (name "/V1+") (class "Default")
      (node (ref "MOTOR1") (pin "1") (pinfunction "1_1") (pintype "passive"))
      (node (ref "U2") (pin "4") (pinfunction "AOUT2_4") (pintype "passive"))
    )
    (net (code "43") (name "/V1-") (class "Default")
      (node (ref "MOTOR1") (pin "6") (pinfunction "6_6") (pintype "passive"))
      (node (ref "U2") (pin "2") (pinfunction "AOUT1_2") (pintype "passive"))
    )
    (net (code "44") (name "/V2+") (class "Default")
      (node (ref "MOTOR2") (pin "1") (pinfunction "1_1") (pintype "passive"))
      (node (ref "U2") (pin "7") (pinfunction "BOUT1_7") (pintype "passive"))
    )
    (net (code "45") (name "/V2-") (class "Default")
      (node (ref "MOTOR2") (pin "6") (pinfunction "6_6") (pintype "passive"))
      (node (ref "U2") (pin "5") (pinfunction "BOUT2_5") (pintype "passive"))
    )
    (net (code "46") (name "/VH1-") (class "Default")
      (node (ref "D3") (pin "2") (pinfunction "A_2") (pintype "passive"))
      (node (ref "MOTOR3") (pin "2") (pinfunction "2_2") (pintype "passive"))
      (node (ref "U12") (pin "3") (pinfunction "D_3") (pintype "passive"))
    )
    (net (code "47") (name "/VH2-") (class "Default")
      (node (ref "D4") (pin "2") (pinfunction "A_2") (pintype "passive"))
      (node (ref "MOTOR3") (pin "4") (pinfunction "4_4") (pintype "passive"))
      (node (ref "U6") (pin "3") (pinfunction "D_3") (pintype "passive"))
    )
    (net (code "48") (name "/VH3-") (class "Default")
      (node (ref "D5") (pin "2") (pinfunction "A_2") (pintype "passive"))
      (node (ref "MOTOR4") (pin "4") (pinfunction "4_4") (pintype "passive"))
      (node (ref "U7") (pin "3") (pinfunction "D_3") (pintype "passive"))
    )
    (net (code "49") (name "/VH4-") (class "Default")
      (node (ref "D6") (pin "2") (pinfunction "A_2") (pintype "passive"))
      (node (ref "MOTOR4") (pin "2") (pinfunction "2_2") (pintype "passive"))
      (node (ref "U8") (pin "3") (pinfunction "D_3") (pintype "passive"))
    )
    (net (code "50") (name "AGND") (class "Default")
      (node (ref "ADC1") (pin "6") (pinfunction "6_6") (pintype "passive"))
      (node (ref "LS1") (pin "1") (pinfunction "1_1") (pintype "passive"))
      (node (ref "LS2") (pin "1") (pinfunction "1_1") (pintype "passive"))
      (node (ref "LS3") (pin "1") (pinfunction "1_1") (pintype "passive"))
      (node (ref "LS4") (pin "1") (pinfunction "1_1") (pintype "passive"))
      (node (ref "R25") (pin "1") (pinfunction "1_1") (pintype "passive"))
      (node (ref "R31") (pin "1") (pinfunction "1_1") (pintype "passive"))
      (node (ref "R34") (pin "1") (pinfunction "1_1") (pintype "passive"))
      (node (ref "R37") (pin "1") (pinfunction "1_1") (pintype "passive"))
      (node (ref "R40") (pin "1") (pinfunction "1_1") (pintype "passive"))
    )
    (net (code "51") (name "GND") (class "Default")
      (node (ref "3.3V") (pin "2") (pinfunction "2_2") (pintype "passive"))
      (node (ref "4.2V") (pin "2") (pinfunction "2_2") (pintype "passive"))
      (node (ref "5V") (pin "2") (pinfunction "2_2") (pintype "passive"))
      (node (ref "BLUETOOTH1") (pin "2") (pinfunction "2_2") (pintype "passive"))
      (node (ref "C1") (pin "1") (pinfunction "1_1") (pintype "passive"))
      (node (ref "C10") (pin "1") (pinfunction "1_1") (pintype "passive"))
      (node (ref "C11") (pin "1") (pinfunction "1_1") (pintype "passive"))
      (node (ref "C12") (pin "2") (pinfunction "2_2") (pintype "passive"))
      (node (ref "C13") (pin "1") (pinfunction "1_1") (pintype "passive"))
      (node (ref "C14") (pin "1") (pinfunction "1_1") (pintype "passive"))
      (node (ref "C15") (pin "1") (pinfunction "1_1") (pintype "passive"))
      (node (ref "C16") (pin "1") (pinfunction "1_1") (pintype "passive"))
      (node (ref "C18") (pin "1") (pinfunction "1_1") (pintype "passive"))
      (node (ref "C19") (pin "2") (pinfunction "2_2") (pintype "passive"))
      (node (ref "C2") (pin "1") (pinfunction "1_1") (pintype "passive"))
      (node (ref "C20") (pin "1") (pinfunction "1_1") (pintype "passive"))
      (node (ref "C21") (pin "2") (pinfunction "2_2") (pintype "passive"))
      (node (ref "C22") (pin "1") (pinfunction "1_1") (pintype "passive"))
      (node (ref "C3") (pin "1") (pinfunction "1_1") (pintype "passive"))
      (node (ref "C4") (pin "2") (pinfunction "2_2") (pintype "passive"))
      (node (ref "C5") (pin "2") (pinfunction "2_2") (pintype "passive"))
      (node (ref "C6") (pin "2") (pinfunction "2_2") (pintype "passive"))
      (node (ref "C7") (pin "2") (pinfunction "2_2") (pintype "passive"))
      (node (ref "C8") (pin "2") (pinfunction "2_2") (pintype "passive"))
      (node (ref "C9") (pin "2") (pinfunction "2_2") (pintype "passive"))
      (node (ref "DI0") (pin "2") (pinfunction "2_2") (pintype "passive"))
      (node (ref "DI1") (pin "2") (pinfunction "2_2") (pintype "passive"))
      (node (ref "DI2") (pin "3") (pinfunction "3_3") (pintype "passive"))
      (node (ref "DI3") (pin "3") (pinfunction "3_3") (pintype "passive"))
      (node (ref "DI5") (pin "6") (pinfunction "6_6") (pintype "passive"))
      (node (ref "DOWN") (pin "2") (pinfunction "2_2") (pintype "passive"))
      (node (ref "ENCODER1") (pin "1") (pinfunction "1_1") (pintype "passive"))
      (node (ref "ENCODER2") (pin "1") (pinfunction "1_1") (pintype "passive"))
      (node (ref "H1") (pin "2") (pinfunction "2_2") (pintype "passive"))
      (node (ref "H1") (pin "4") (pinfunction "4_4") (pintype "passive"))
      (node (ref "LOAD1") (pin "3") (pinfunction "3_3") (pintype "passive"))
      (node (ref "MOTOR1") (pin "5") (pinfunction "5_5") (pintype "passive"))
      (node (ref "MOTOR2") (pin "5") (pinfunction "5_5") (pintype "passive"))
      (node (ref "MPU6050") (pin "2") (pinfunction "2_2") (pintype "passive"))
      (node (ref "NO1") (pin "2") (pinfunction "GND_2") (pintype "passive"))
      (node (ref "NO1") (pin "4") (pinfunction "GND_4") (pintype "passive"))
      (node (ref "OK") (pin "2") (pinfunction "2_2") (pintype "passive"))
      (node (ref "OLED1") (pin "1") (pinfunction "GND_1") (pintype "passive"))
      (node (ref "POWER_BATTERY1") (pin "1") (pinfunction "1_1") (pintype "passive"))
      (node (ref "Q1") (pin "2") (pinfunction "E_2") (pintype "passive"))
      (node (ref "R1") (pin "2") (pinfunction "2_2") (pintype "passive"))
      (node (ref "R15") (pin "1") (pinfunction "1_1") (pintype "passive"))
      (node (ref "R16") (pin "1") (pinfunction "1_1") (pintype "passive"))
      (node (ref "R17") (pin "1") (pinfunction "1_1") (pintype "passive"))
      (node (ref "R18") (pin "1") (pinfunction "1_1") (pintype "passive"))
      (node (ref "R19") (pin "1") (pinfunction "1_1") (pintype "passive"))
      (node (ref "R2") (pin "1") (pinfunction "1_1") (pintype "passive"))
      (node (ref "R25") (pin "2") (pinfunction "2_2") (pintype "passive"))
      (node (ref "R44") (pin "1") (pinfunction "1_1") (pintype "passive"))
      (node (ref "R5") (pin "2") (pinfunction "2_2") (pintype "passive"))
      (node (ref "R8") (pin "2") (pinfunction "2_2") (pintype "passive"))
      (node (ref "RST") (pin "2") (pinfunction "2_2") (pintype "passive"))
      (node (ref "STEER1") (pin "5") (pinfunction "5_5") (pintype "passive"))
      (node (ref "STEER1") (pin "6") (pinfunction "6_6") (pintype "passive"))
      (node (ref "SW2") (pin "3") (pinfunction "3_3") (pintype "passive"))
      (node (ref "SW2") (pin "C") (pinfunction "C_C") (pintype "passive"))
      (node (ref "U1") (pin "23") (pinfunction "VSS_1_23") (pintype "passive"))
      (node (ref "U1") (pin "35") (pinfunction "VSS_2_35") (pintype "passive"))
      (node (ref "U1") (pin "47") (pinfunction "VSS_3_47") (pintype "passive"))
      (node (ref "U1") (pin "8") (pinfunction "VSSA_8") (pintype "passive"))
      (node (ref "U12") (pin "2") (pinfunction "S_2") (pintype "passive"))
      (node (ref "U14") (pin "2") (pinfunction "GND_2") (pintype "passive"))
      (node (ref "U2") (pin "13") (pinfunction "GND_13") (pintype "passive"))
      (node (ref "U3") (pin "2") (pinfunction "GND_2") (pintype "passive"))
      (node (ref "U4") (pin "2") (pinfunction "GND_2") (pintype "passive"))
      (node (ref "U6") (pin "2") (pinfunction "S_2") (pintype "passive"))
      (node (ref "U7") (pin "2") (pinfunction "S_2") (pintype "passive"))
      (node (ref "U8") (pin "2") (pinfunction "S_2") (pintype "passive"))
      (node (ref "UP") (pin "2") (pinfunction "2_2") (pintype "passive"))
      (node (ref "V_ADJ") (pin "2") (pinfunction "2_2") (pintype "passive"))
      (node (ref "WIFI") (pin "7") (pinfunction "7_7") (pintype "passive"))
    )
    (net (code "52") (name "Net-(3.3V-Pad1)") (class "Default")
      (node (ref "3.3V") (pin "1") (pinfunction "1_1") (pintype "passive"))
      (node (ref "R13") (pin "1") (pinfunction "1_1") (pintype "passive"))
    )
    (net (code "53") (name "Net-(4.2V-Pad1)") (class "Default")
      (node (ref "4.2V") (pin "1") (pinfunction "1_1") (pintype "passive"))
      (node (ref "R10") (pin "1") (pinfunction "1_1") (pintype "passive"))
    )
    (net (code "54") (name "Net-(5V-Pad1)") (class "Default")
      (node (ref "5V") (pin "1") (pinfunction "1_1") (pintype "passive"))
      (node (ref "R12") (pin "1") (pinfunction "1_1") (pintype "passive"))
    )
    (net (code "55") (name "Net-(D1-A)") (class "Default")
      (node (ref "D1") (pin "2") (pinfunction "A_2") (pintype "passive"))
      (node (ref "L1") (pin "1") (pinfunction "1_1") (pintype "passive"))
      (node (ref "U3") (pin "1") (pinfunction "SW_1") (pintype "passive"))
    )
    (net (code "56") (name "Net-(D2-A)") (class "Default")
      (node (ref "D2") (pin "2") (pinfunction "A_2") (pintype "passive"))
      (node (ref "L2") (pin "1") (pinfunction "1_1") (pintype "passive"))
      (node (ref "U4") (pin "1") (pinfunction "SW_1") (pintype "passive"))
    )
    (net (code "57") (name "Net-(LS1-Pad2)") (class "Default")
      (node (ref "LS1") (pin "2") (pinfunction "2_2") (pintype "passive"))
      (node (ref "R32") (pin "2") (pinfunction "2_2") (pintype "passive"))
      (node (ref "R33") (pin "1") (pinfunction "1_1") (pintype "passive"))
    )
    (net (code "58") (name "Net-(LS2-Pad2)") (class "Default")
      (node (ref "LS2") (pin "2") (pinfunction "2_2") (pintype "passive"))
      (node (ref "R35") (pin "2") (pinfunction "2_2") (pintype "passive"))
      (node (ref "R36") (pin "1") (pinfunction "1_1") (pintype "passive"))
    )
    (net (code "59") (name "Net-(LS3-Pad2)") (class "Default")
      (node (ref "LS3") (pin "2") (pinfunction "2_2") (pintype "passive"))
      (node (ref "R38") (pin "3") (pinfunction "3_3") (pintype "passive"))
      (node (ref "R39") (pin "1") (pinfunction "1_1") (pintype "passive"))
    )
    (net (code "60") (name "Net-(LS4-Pad2)") (class "Default")
      (node (ref "LS4") (pin "2") (pinfunction "2_2") (pintype "passive"))
      (node (ref "R41") (pin "3") (pinfunction "3_3") (pintype "passive"))
      (node (ref "R42") (pin "1") (pinfunction "1_1") (pintype "passive"))
    )
    (net (code "61") (name "Net-(POWER_BATTERY1-Pad2)") (class "Default")
      (node (ref "POWER_BATTERY1") (pin "2") (pinfunction "2_2") (pintype "passive"))
      (node (ref "U5") (pin "1") (pinfunction "1_1") (pintype "passive"))
    )
    (net (code "62") (name "Net-(Q1-B)") (class "Default")
      (node (ref "Q1") (pin "1") (pinfunction "B_1") (pintype "passive"))
      (node (ref "R43") (pin "2") (pinfunction "2_2") (pintype "passive"))
      (node (ref "R44") (pin "2") (pinfunction "2_2") (pintype "passive"))
    )
    (net (code "63") (name "Net-(Q1-C)") (class "Default")
      (node (ref "Q1") (pin "3") (pinfunction "C_3") (pintype "passive"))
      (node (ref "U9") (pin "2") (pinfunction "2_2") (pintype "passive"))
    )
    (net (code "64") (name "Net-(R11-Pad1)") (class "Default")
      (node (ref "R11") (pin "1") (pinfunction "1_1") (pintype "passive"))
      (node (ref "V_ADJ") (pin "1") (pinfunction "1_1") (pintype "passive"))
    )
    (net (code "65") (name "Net-(R14-Pad2)") (class "Default")
      (node (ref "R14") (pin "2") (pinfunction "2_2") (pintype "passive"))
      (node (ref "U10") (pin "2") (pinfunction "2_2") (pintype "passive"))
      (node (ref "U10") (pin "3") (pinfunction "3_3") (pintype "passive"))
    )
    (net (code "66") (name "Net-(R26-Pad1)") (class "Default")
      (node (ref "R26") (pin "1") (pinfunction "1_1") (pintype "passive"))
      (node (ref "WIFI") (pin "6") (pinfunction "6_6") (pintype "passive"))
    )
    (net (code "67") (name "Net-(U1-BOOT0)") (class "Default")
      (node (ref "R1") (pin "1") (pinfunction "1_1") (pintype "passive"))
      (node (ref "U1") (pin "44") (pinfunction "BOOT0_44") (pintype "passive"))
    )
    (net (code "68") (name "Net-(U1-PB2)") (class "Default")
      (node (ref "R2") (pin "2") (pinfunction "2_2") (pintype "passive"))
      (node (ref "U1") (pin "20") (pinfunction "PB2_20") (pintype "passive"))
    )
    (net (code "69") (name "Net-(U2-AISEN)") (class "Default")
      (node (ref "R15") (pin "2") (pinfunction "2_2") (pintype "passive"))
      (node (ref "U2") (pin "3") (pinfunction "AISEN_3") (pintype "passive"))
      (node (ref "U2") (pin "6") (pinfunction "BISEN_6") (pintype "passive"))
    )
    (net (code "70") (name "Net-(U2-VCP)") (class "Default")
      (node (ref "C17") (pin "1") (pinfunction "1_1") (pintype "passive"))
      (node (ref "U2") (pin "11") (pinfunction "VCP_11") (pintype "passive"))
    )
    (net (code "71") (name "Net-(U2-VINT)") (class "Default")
      (node (ref "C19") (pin "1") (pinfunction "1_1") (pintype "passive"))
      (node (ref "U2") (pin "14") (pinfunction "VINT_14") (pintype "passive"))
    )
    (net (code "72") (name "Net-(U2-nSleep)") (class "Default")
      (node (ref "R14") (pin "1") (pinfunction "1_1") (pintype "passive"))
      (node (ref "U2") (pin "1") (pinfunction "nSleep_1") (pintype "passive"))
    )
    (net (code "73") (name "Net-(U3-EN)") (class "Default")
      (node (ref "R6") (pin "2") (pinfunction "2_2") (pintype "passive"))
      (node (ref "U3") (pin "4") (pinfunction "EN_4") (pintype "passive"))
    )
    (net (code "74") (name "Net-(U3-FB)") (class "Default")
      (node (ref "R4") (pin "1") (pinfunction "1_1") (pintype "passive"))
      (node (ref "R5") (pin "1") (pinfunction "1_1") (pintype "passive"))
      (node (ref "U3") (pin "3") (pinfunction "FB_3") (pintype "passive"))
    )
    (net (code "75") (name "Net-(U4-EN)") (class "Default")
      (node (ref "R9") (pin "2") (pinfunction "2_2") (pintype "passive"))
      (node (ref "U4") (pin "4") (pinfunction "EN_4") (pintype "passive"))
    )
    (net (code "76") (name "Net-(U4-FB)") (class "Default")
      (node (ref "R7") (pin "1") (pinfunction "1_1") (pintype "passive"))
      (node (ref "R8") (pin "1") (pinfunction "1_1") (pintype "passive"))
      (node (ref "U4") (pin "3") (pinfunction "FB_3") (pintype "passive"))
    )
    (net (code "77") (name "unconnected-(BLUETOOTH1-Pad5)") (class "Default")
      (node (ref "BLUETOOTH1") (pin "5") (pinfunction "5_5") (pintype "passive+no_connect"))
    )
    (net (code "78") (name "unconnected-(BLUETOOTH1-Pad6)") (class "Default")
      (node (ref "BLUETOOTH1") (pin "6") (pinfunction "6_6") (pintype "passive+no_connect"))
    )
    (net (code "79") (name "unconnected-(ENCODER1-Pad5)") (class "Default")
      (node (ref "ENCODER1") (pin "5") (pinfunction "5_5") (pintype "passive+no_connect"))
    )
    (net (code "80") (name "unconnected-(ENCODER1-Pad6)") (class "Default")
      (node (ref "ENCODER1") (pin "6") (pinfunction "6_6") (pintype "passive+no_connect"))
    )
    (net (code "81") (name "unconnected-(ENCODER2-Pad5)") (class "Default")
      (node (ref "ENCODER2") (pin "5") (pinfunction "5_5") (pintype "passive+no_connect"))
    )
    (net (code "82") (name "unconnected-(ENCODER2-Pad6)") (class "Default")
      (node (ref "ENCODER2") (pin "6") (pinfunction "6_6") (pintype "passive+no_connect"))
    )
    (net (code "83") (name "unconnected-(R38-Pad1)") (class "Default")
      (node (ref "R38") (pin "1") (pinfunction "1_1") (pintype "passive+no_connect"))
    )
    (net (code "84") (name "unconnected-(R41-Pad1)") (class "Default")
      (node (ref "R41") (pin "1") (pinfunction "1_1") (pintype "passive+no_connect"))
    )
    (net (code "85") (name "unconnected-(U2-nFault-Pad8)") (class "Default")
      (node (ref "U2") (pin "8") (pinfunction "nFault_8") (pintype "passive+no_connect"))
    )
    (net (code "86") (name "unconnected-(U3-NC-Pad6)") (class "Default")
      (node (ref "U3") (pin "6") (pinfunction "NC_6") (pintype "passive+no_connect"))
    )
    (net (code "87") (name "unconnected-(U4-NC-Pad6)") (class "Default")
      (node (ref "U4") (pin "6") (pinfunction "NC_6") (pintype "passive+no_connect"))
    )
    (net (code "88") (name "unconnected-(U14-NC-Pad4)") (class "Default")
      (node (ref "U14") (pin "4") (pinfunction "NC_4") (pintype "passive+no_connect"))
    )
    (net (code "89") (name "unconnected-(WIFI-Pad3)") (class "Default")
      (node (ref "WIFI") (pin "3") (pinfunction "3_3") (pintype "passive+no_connect"))
    )
    (net (code "90") (name "unconnected-(WIFI-Pad4)") (class "Default")
      (node (ref "WIFI") (pin "4") (pinfunction "4_4") (pintype "passive+no_connect"))
    )
    (net (code "91") (name "unconnected-(WIFI-Pad5)") (class "Default")
      (node (ref "WIFI") (pin "5") (pinfunction "5_5") (pintype "passive+no_connect"))
    )
  )
)
